# Latch.net
KiCad netlist of a schematic drawn in Altium Designer
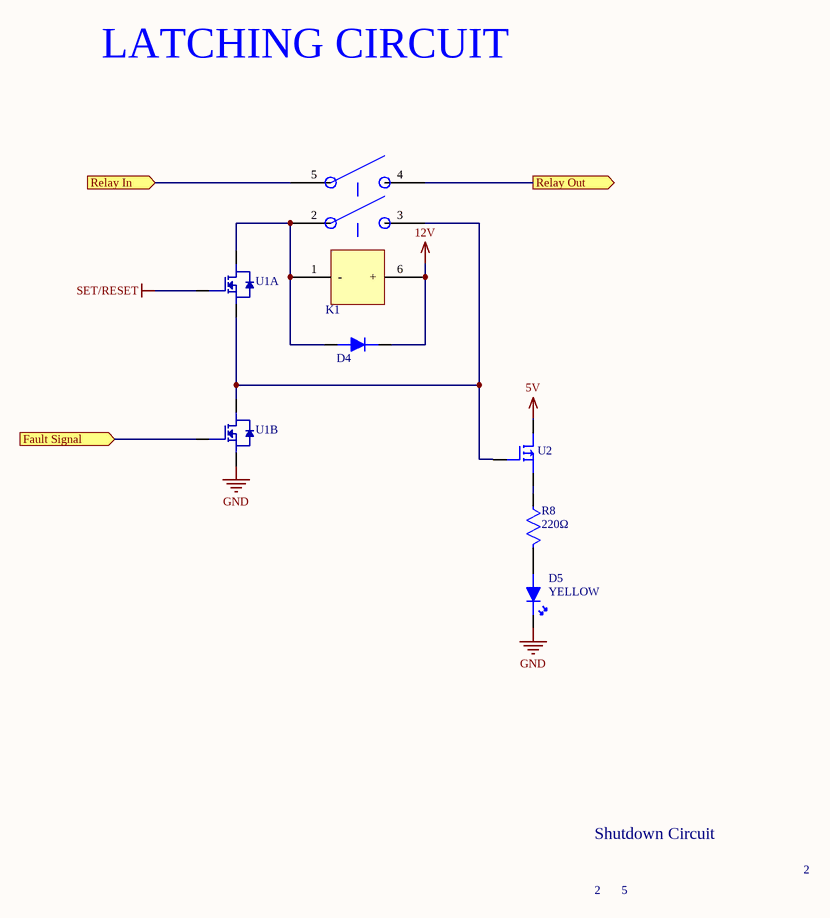
[diagram p0: Latch.SchDoc]

(export (version "E")
  (design (tool "Eeschema 10.0.6"))
  (components
    (comp (ref "D4")
      (value "SD560BTR")
      (footprint "DIODE")
      (description "DIODE GEN PURP 600V 5A SMB")
      (fields (field (name "MANUFACTURER") "SMC"))
      (libsource (lib "sdc_prech_schlib") (part "SD560BTR"))
    )
    (comp (ref "D5")
      (value "YELLOW")
      (footprint "LED 0603")
      (description "LED YELLOW CLEAR SMD")
      (fields
        (field (name "MANUFACTURER") "Vishay Lite-On")
        (field (name "MANUFACTURER PART NUMBER") "LTST-C191KSKT")
      )
      (libsource (lib "sdc_prech_schlib") (part "LTST-C191KSKT"))
    )
    (comp (ref "K1")
      (value "5-1419124-6")
      (footprint "RELAY DPST SDC")
      (description "General Purpose Relay, Osa Series, Power, Non Latching, Dpst-No, 12 Vdc, 3 A Rohs Compliant: Yes")
      (fields (field (name "MANUFACTURER") "TE Connectivity"))
      (libsource (lib "sdc_prech_schlib") (part "5-1419124-6"))
    )
    (comp (ref "R8")
      (value "220Ω")
      (footprint "RESISTOR 0603")
      (description "RES SMD 220 OHM 5% 1/10W 0603")
      (fields
        (field (name "MANUFACTURER") "Vishay")
        (field (name "MANUFACTURER PART NUMBER") "CRCW0603220RJNEA")
      )
      (libsource (lib "sdc_prech_schlib") (part "CRCW0603220RJNEA"))
    )
    (comp (ref "U1")
      (value "SSM6N7002CFU,LF")
      (footprint "N-MOSFET (2 FETS)")
      (description "MOSFET 2N-CH 60V 0.17A US6")
      (fields (field (name "MANUFACTURER") "Toshiba"))
      (libsource (lib "sdc_prech_schlib") (part "SSM6N7002CFU,LF"))
    )
    (comp (ref "U2")
      (value "NTD2955T4GOSCT-ND")
      (footprint "DPAK-TO252")
      (description "MOSFET P-CH 60V 12A DPAK")
      (fields
        (field (name "MANUFACTURER") "ON Semiconductor")
        (field (name "MANUFACTURER PART NUMBER") "NTD2955T4G")
      )
      (libsource (lib "Transistors") (part "P-FET-60V-12A"))
    )
  )
  (nets
    (net (code "1") (name "/Fault Signal") (class "Default")
      (node (ref "U1") (pin "5") (pinfunction "G2_5") (pintype "passive"))
    )
    (net (code "2") (name "/Relay In") (class "Default") (node (ref "K1") (pin "5") (pintype "passive")))
    (net (code "3") (name "/Relay Out") (class "Default") (node (ref "K1") (pin "4") (pintype "passive")))
    (net (code "4") (name "5V") (class "Default")
      (node (ref "U2") (pin "2") (pinfunction "2_2") (pintype "passive"))
    )
    (net (code "5") (name "12V") (class "Default")
      (node (ref "D4") (pin "2") (pinfunction "2_2") (pintype "passive"))
      (node (ref "K1") (pin "6") (pinfunction "+_6") (pintype "passive"))
    )
    (net (code "6") (name "GND") (class "Default")
      (node (ref "D5") (pin "2") (pinfunction "2_2") (pintype "passive"))
      (node (ref "U1") (pin "4") (pinfunction "S2_4") (pintype "passive"))
    )
    (net (code "7") (name "Net-(D5-Pad1)") (class "Default")
      (node (ref "D5") (pin "1") (pinfunction "1_1") (pintype "passive"))
      (node (ref "R8") (pin "2") (pinfunction "2_2") (pintype "passive"))
    )
    (net (code "8") (name "Net-(K1--)") (class "Default")
      (node (ref "D4") (pin "1") (pinfunction "1_1") (pintype "passive"))
      (node (ref "K1") (pin "1") (pinfunction "-_1") (pintype "passive"))
      (node (ref "K1") (pin "2") (pintype "passive"))
      (node (ref "U1") (pin "6") (pinfunction "D1_6") (pintype "passive"))
    )
    (net (code "9") (name "Net-(R8-Pad1)") (class "Default")
      (node (ref "R8") (pin "1") (pinfunction "1_1") (pintype "passive"))
      (node (ref "U2") (pin "3") (pinfunction "3_3") (pintype "passive"))
    )
    (net (code "10") (name "Net-(U1A-S1)") (class "Default")
      (node (ref "K1") (pin "3") (pintype "passive"))
      (node (ref "U1") (pin "1") (pinfunction "S1_1") (pintype "passive"))
      (node (ref "U1") (pin "3") (pinfunction "D2_3") (pintype "passive"))
    )
    (net (code "11") (name "SET{slash}RESET") (class "Default")
      (node (ref "U1") (pin "2") (pinfunction "G1_2") (pintype "passive"))
    )
    (net (code "12") (name "unconnected-(U2-Pad1)") (class "Default")
      (node (ref "U2") (pin "1") (pinfunction "1_1") (pintype "passive"))
    )
  )
)
